# Adafruit_Trinket_5V.net
KiCad netlist of a schematic drawn in EAGLE
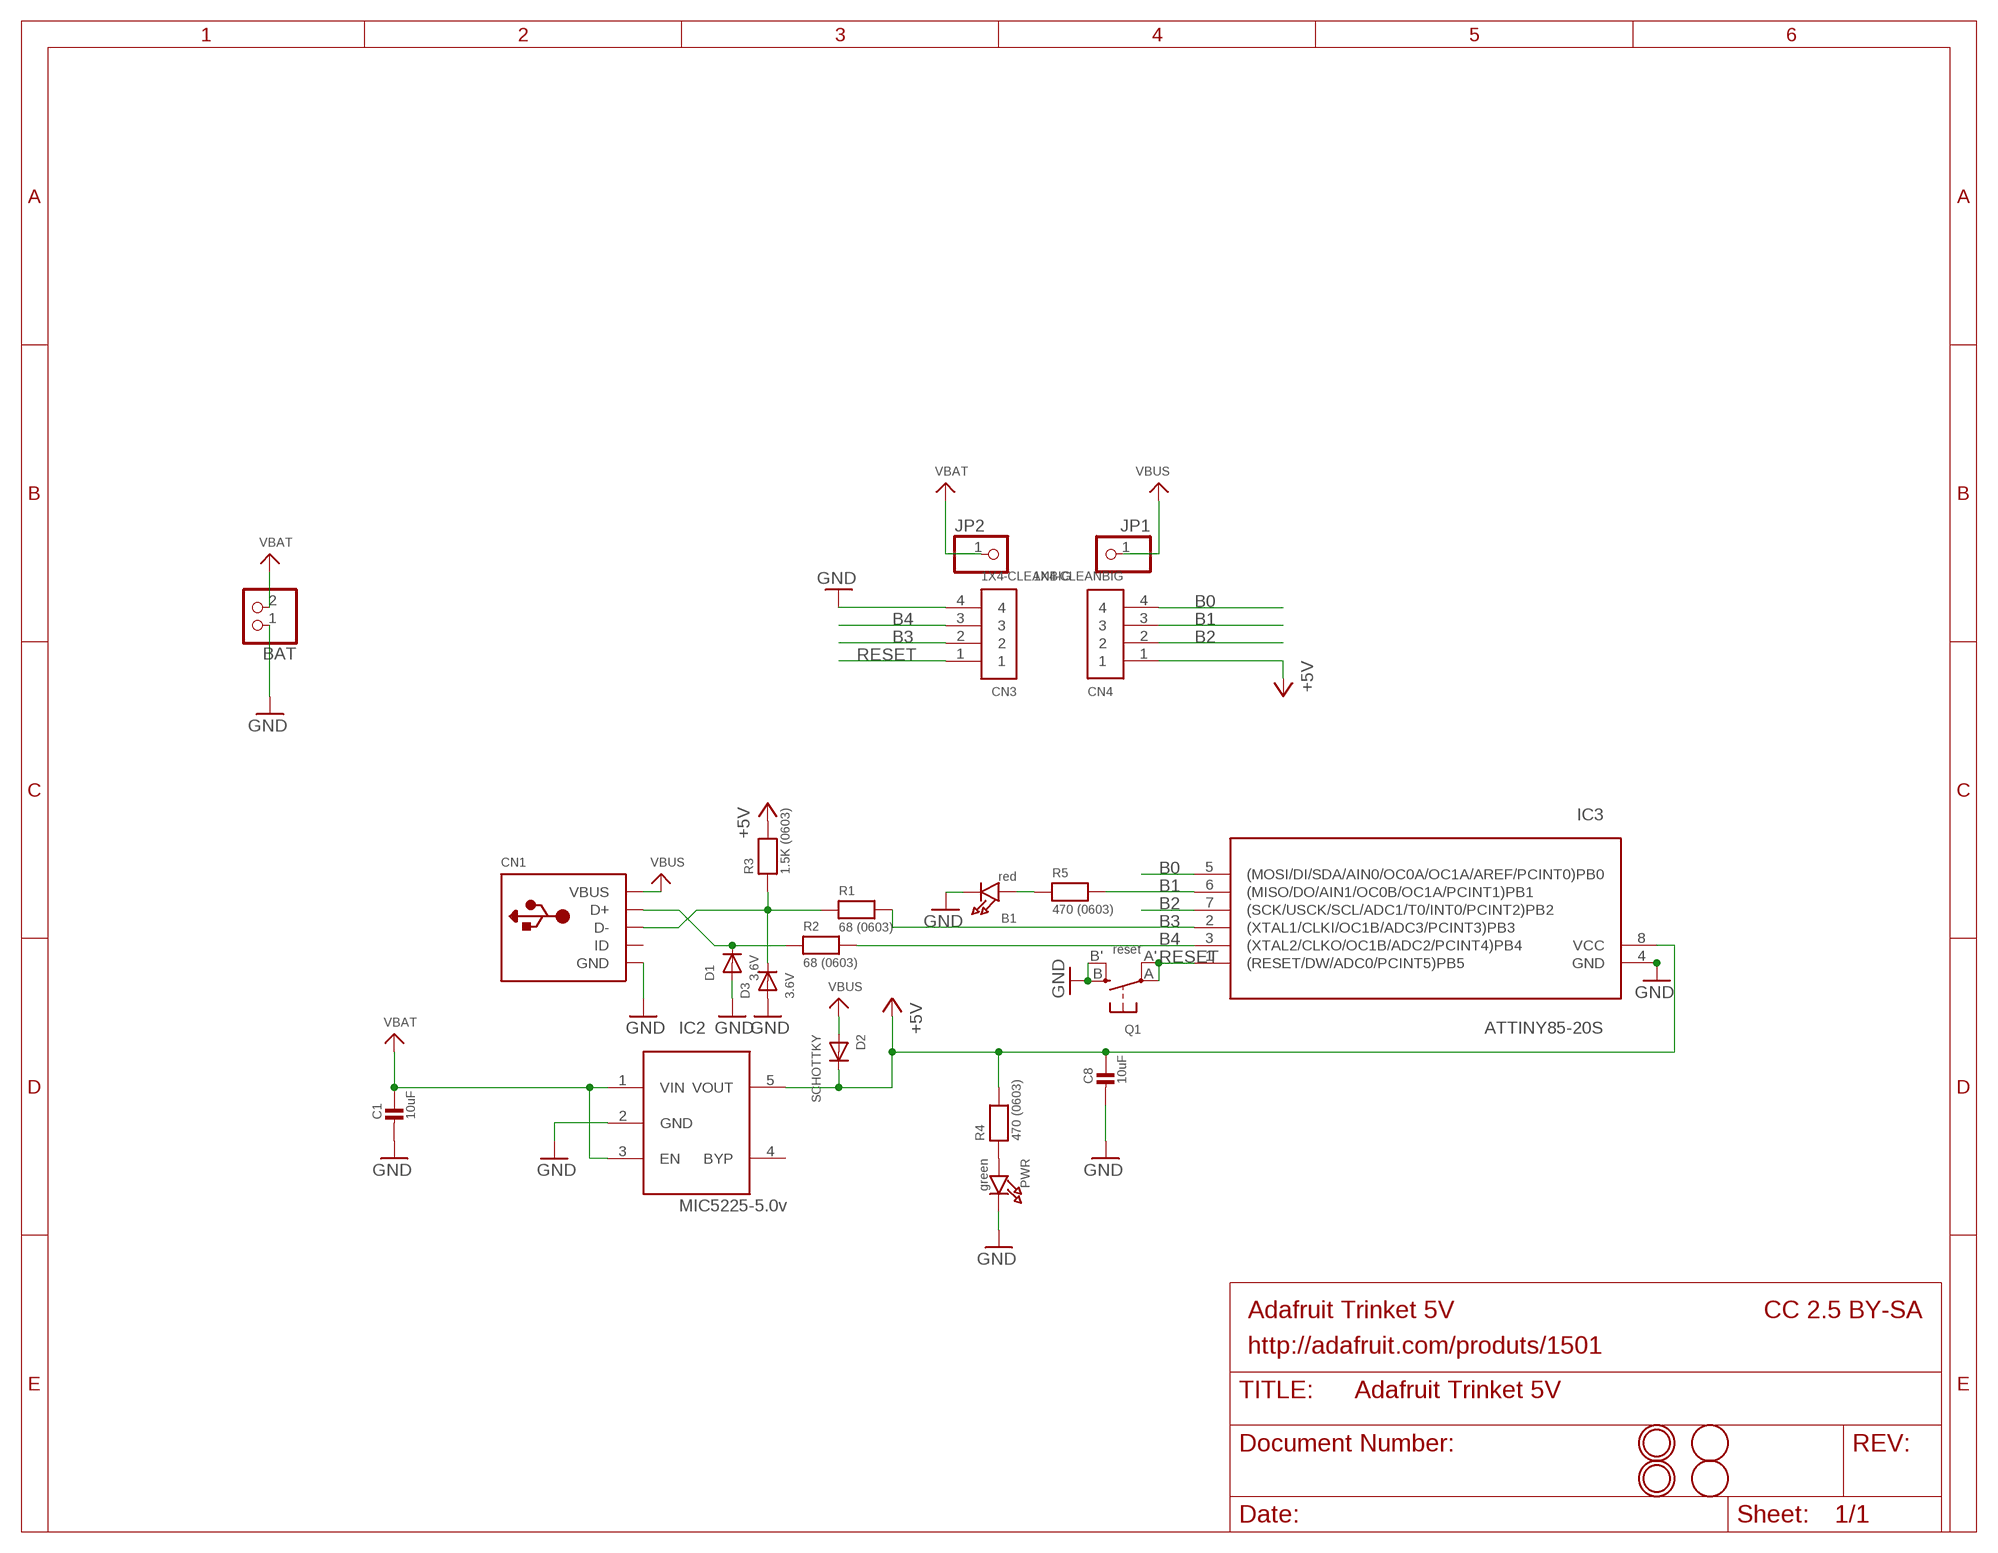
[diagram p0: schematic, sheet 1]

(export (version "E")
  (design (tool "Eeschema 10.0.6"))
  (components
    (comp (ref "B1")
      (value "red")
      (footprint "eagle-import:CHIPLED_0805_NOOUTLINE")
      (libsource (lib "eagle-import") (part "LED0805_NOOUTLINE"))
    )
    (comp (ref "BAT")
      (value "CON_JST_PH_2PIN")
      (footprint "eagle-import:JSTPH2")
      (libsource (lib "eagle-import") (part "CON_JST_PH_2PIN"))
    )
    (comp (ref "C1")
      (value "10uF")
      (footprint "eagle-import:0805-NO")
      (libsource (lib "eagle-import") (part "CAP_CERAMIC0805-NOOUTLINE"))
    )
    (comp (ref "C8")
      (value "10uF")
      (footprint "eagle-import:0805-NO")
      (libsource (lib "eagle-import") (part "CAP_CERAMIC0805-NOOUTLINE"))
    )
    (comp (ref "CN1")
      (value "USBMINIB")
      (footprint "eagle-import:USB-MINIB")
      (libsource (lib "eagle-import") (part "USBMINIB"))
    )
    (comp (ref "CN3")
      (value "1X4-CLEANBIG")
      (footprint "eagle-import:1X04-CLEANBIG")
      (libsource (lib "eagle-import") (part "1X4-CLEANBIG"))
    )
    (comp (ref "CN4")
      (value "1X4-CLEANBIG")
      (footprint "eagle-import:1X04-CLEANBIG")
      (libsource (lib "eagle-import") (part "1X4-CLEANBIG"))
    )
    (comp (ref "D1")
      (value "3.6V")
      (footprint "eagle-import:SOD-323")
      (libsource (lib "eagle-import") (part "DIODESOD-323"))
    )
    (comp (ref "D2")
      (value "SCHOTTKY")
      (footprint "eagle-import:SOD-123FL")
      (libsource (lib "eagle-import") (part "DIODE_SOD-123FL"))
    )
    (comp (ref "D3")
      (value "3.6V")
      (footprint "eagle-import:SOD-323")
      (libsource (lib "eagle-import") (part "DIODESOD-323"))
    )
    (comp (ref "IC2")
      (value "MIC5225-5.0v")
      (footprint "eagle-import:SOT23-5L")
      (libsource (lib "eagle-import") (part "LP298XS"))
    )
    (comp (ref "IC3")
      (value "ATTINY85-20S")
      (footprint "eagle-import:SOIC8")
      (libsource (lib "eagle-import") (part "ATTINY85SV-10"))
    )
    (comp (ref "JP1")
      (value "PINHD-1X1CB")
      (footprint "eagle-import:1X01-CLEANBIG")
      (libsource (lib "eagle-import") (part "PINHD-1X1CB"))
    )
    (comp (ref "JP2")
      (value "PINHD-1X1CB")
      (footprint "eagle-import:1X01-CLEANBIG")
      (libsource (lib "eagle-import") (part "PINHD-1X1CB"))
    )
    (comp (ref "PWR")
      (value "green")
      (footprint "eagle-import:CHIPLED_0805_NOOUTLINE")
      (libsource (lib "eagle-import") (part "LED0805_NOOUTLINE"))
    )
    (comp (ref "Q1")
      (value "reset")
      (footprint "eagle-import:BTN_KMR2_4.6X2.8")
      (libsource (lib "eagle-import") (part "SWITCH_TACT_SMT4.6X2.8"))
    )
    (comp (ref "R1")
      (value "68 (0603)")
      (footprint "eagle-import:0603-NO")
      (libsource (lib "eagle-import") (part "RESISTOR_0603_NOOUT"))
    )
    (comp (ref "R2")
      (value "68 (0603)")
      (footprint "eagle-import:0603-NO")
      (libsource (lib "eagle-import") (part "RESISTOR_0603_NOOUT"))
    )
    (comp (ref "R3")
      (value "1.5K (0603)")
      (footprint "eagle-import:0603-NO")
      (libsource (lib "eagle-import") (part "RESISTOR_0603_NOOUT"))
    )
    (comp (ref "R4")
      (value "470 (0603)")
      (footprint "eagle-import:0603-NO")
      (libsource (lib "eagle-import") (part "RESISTOR_0603_NOOUT"))
    )
    (comp (ref "R5")
      (value "470 (0603)")
      (footprint "eagle-import:0603-NO")
      (libsource (lib "eagle-import") (part "RESISTOR_0603_NOOUT"))
    )
    (comp (ref "U$1")
      (value "FIDUCIAL")
      (footprint "eagle-import:FIDUCIAL_1MM")
      (libsource (lib "eagle-import") (part "FIDUCIAL"))
    )
    (comp (ref "U$6")
      (value "FIDUCIAL")
      (footprint "eagle-import:FIDUCIAL_1MM")
      (libsource (lib "eagle-import") (part "FIDUCIAL"))
    )
    (comp (ref "U$8")
      (value "MOUNTINGHOLE2.0")
      (footprint "eagle-import:MOUNTINGHOLE_2.0_PLATED")
      (libsource (lib "eagle-import") (part "MOUNTINGHOLE2.0"))
    )
    (comp (ref "U$9")
      (value "MOUNTINGHOLE2.0")
      (footprint "eagle-import:MOUNTINGHOLE_2.0_PLATED")
      (libsource (lib "eagle-import") (part "MOUNTINGHOLE2.0"))
    )
  )
  (nets
    (net (code "1") (name "+5V") (class "Default")
      (node (ref "C8") (pin "1") (pinfunction "1_1") (pintype "passive"))
      (node (ref "CN4") (pin "1") (pinfunction "1_1") (pintype "bidirectional"))
      (node (ref "D2") (pin "C") (pinfunction "C_C") (pintype "passive"))
      (node (ref "IC2") (pin "5") (pinfunction "VOUT_5") (pintype "bidirectional"))
      (node (ref "IC3") (pin "8") (pinfunction "VCC_8") (pintype "bidirectional"))
      (node (ref "R3") (pin "2") (pinfunction "2_2") (pintype "passive"))
      (node (ref "R4") (pin "2") (pinfunction "2_2") (pintype "passive"))
    )
    (net (code "2") (name "/B0") (class "Default")
      (node (ref "CN4") (pin "4") (pinfunction "4_4") (pintype "bidirectional"))
      (node (ref "IC3") (pin "5") (pinfunction "(MOSI/DI/SDA/AIN0/OC0A/OC1A/AREF/PCINT0)PB0_5") (pintype "bidirectional"))
    )
    (net (code "3") (name "/B1") (class "Default")
      (node (ref "CN4") (pin "3") (pinfunction "3_3") (pintype "bidirectional"))
      (node (ref "IC3") (pin "6") (pinfunction "(MISO/DO/AIN1/OC0B/OC1A/PCINT1)PB1_6") (pintype "bidirectional"))
      (node (ref "R5") (pin "2") (pinfunction "2_2") (pintype "passive"))
    )
    (net (code "4") (name "/B2") (class "Default")
      (node (ref "CN4") (pin "2") (pinfunction "2_2") (pintype "bidirectional"))
      (node (ref "IC3") (pin "7") (pinfunction "(SCK/USCK/SCL/ADC1/T0/INT0/PCINT2)PB2_7") (pintype "bidirectional"))
    )
    (net (code "5") (name "/B3") (class "Default")
      (node (ref "CN3") (pin "2") (pinfunction "2_2") (pintype "bidirectional"))
      (node (ref "IC3") (pin "2") (pinfunction "(XTAL1/CLKI/OC1B/ADC3/PCINT3)PB3_2") (pintype "bidirectional"))
      (node (ref "R1") (pin "2") (pinfunction "2_2") (pintype "passive"))
    )
    (net (code "6") (name "/B4") (class "Default")
      (node (ref "CN3") (pin "3") (pinfunction "3_3") (pintype "bidirectional"))
      (node (ref "IC3") (pin "3") (pinfunction "(XTAL2/CLKO/OC1B/ADC2/PCINT4)PB4_3") (pintype "bidirectional"))
      (node (ref "R2") (pin "2") (pinfunction "2_2") (pintype "passive"))
    )
    (net (code "7") (name "/RESET") (class "Default")
      (node (ref "CN3") (pin "1") (pinfunction "1_1") (pintype "bidirectional"))
      (node (ref "IC3") (pin "1") (pinfunction "(RESET/DW/ADC0/PCINT5)PB5_1") (pintype "bidirectional"))
      (node (ref "Q1") (pin "A") (pinfunction "P_A") (pintype "passive"))
      (node (ref "Q1") (pin "A'") (pinfunction "P1_A'") (pintype "passive"))
    )
    (net (code "8") (name "GND") (class "Default")
      (node (ref "B1") (pin "C") (pinfunction "C_C") (pintype "passive"))
      (node (ref "BAT") (pin "1") (pinfunction "1_1") (pintype "passive"))
      (node (ref "C1") (pin "2") (pinfunction "2_2") (pintype "passive"))
      (node (ref "C8") (pin "2") (pinfunction "2_2") (pintype "passive"))
      (node (ref "CN1") (pin "GND") (pinfunction "GND_GND") (pintype "power_in"))
      (node (ref "CN1") (pin "GND1") (pinfunction "GND_GND1") (pintype "power_in"))
      (node (ref "CN1") (pin "GND2") (pinfunction "GND_GND2") (pintype "power_in"))
      (node (ref "CN1") (pin "GND3") (pinfunction "GND_GND3") (pintype "power_in"))
      (node (ref "CN1") (pin "GND4") (pinfunction "GND_GND4") (pintype "power_in"))
      (node (ref "CN3") (pin "4") (pinfunction "4_4") (pintype "bidirectional"))
      (node (ref "D1") (pin "A") (pinfunction "A_A") (pintype "passive"))
      (node (ref "D3") (pin "A") (pinfunction "A_A") (pintype "passive"))
      (node (ref "IC2") (pin "2") (pinfunction "GND_2") (pintype "bidirectional"))
      (node (ref "IC3") (pin "4") (pinfunction "GND_4") (pintype "bidirectional"))
      (node (ref "PWR") (pin "C") (pinfunction "C_C") (pintype "passive"))
      (node (ref "Q1") (pin "B") (pinfunction "S_B") (pintype "passive"))
      (node (ref "Q1") (pin "B'") (pinfunction "S1_B'") (pintype "passive"))
    )
    (net (code "9") (name "Net-(B1-PadA)") (class "Default")
      (node (ref "B1") (pin "A") (pinfunction "A_A") (pintype "passive"))
      (node (ref "R5") (pin "1") (pinfunction "1_1") (pintype "passive"))
    )
    (net (code "10") (name "Net-(CN1-PadD+)") (class "Default")
      (node (ref "CN1") (pin "D+") (pinfunction "D+_D+") (pintype "bidirectional"))
      (node (ref "D1") (pin "C") (pinfunction "C_C") (pintype "passive"))
      (node (ref "R2") (pin "1") (pinfunction "1_1") (pintype "passive"))
    )
    (net (code "11") (name "Net-(CN1-PadD-)") (class "Default")
      (node (ref "CN1") (pin "D-") (pinfunction "D-_D-") (pintype "bidirectional"))
      (node (ref "D3") (pin "C") (pinfunction "C_C") (pintype "passive"))
      (node (ref "R1") (pin "1") (pinfunction "1_1") (pintype "passive"))
      (node (ref "R3") (pin "1") (pinfunction "1_1") (pintype "passive"))
    )
    (net (code "12") (name "Net-(PWR-PadA)") (class "Default")
      (node (ref "PWR") (pin "A") (pinfunction "A_A") (pintype "passive"))
      (node (ref "R4") (pin "1") (pinfunction "1_1") (pintype "passive"))
    )
    (net (code "13") (name "VBAT") (class "Default")
      (node (ref "BAT") (pin "2") (pinfunction "2_2") (pintype "passive"))
      (node (ref "C1") (pin "1") (pinfunction "1_1") (pintype "passive"))
      (node (ref "IC2") (pin "1") (pinfunction "VIN_1") (pintype "bidirectional"))
      (node (ref "IC2") (pin "3") (pinfunction "EN_3") (pintype "bidirectional"))
      (node (ref "JP2") (pin "1") (pinfunction "1_1") (pintype "passive"))
    )
    (net (code "14") (name "VBUS") (class "Default")
      (node (ref "CN1") (pin "VBUS") (pinfunction "VBUS_VBUS") (pintype "power_in"))
      (node (ref "D2") (pin "A") (pinfunction "A_A") (pintype "passive"))
      (node (ref "JP1") (pin "1") (pinfunction "1_1") (pintype "passive"))
    )
    (net (code "15") (name "unconnected-(CN1-PadID)") (class "Default")
      (node (ref "CN1") (pin "ID") (pinfunction "ID_ID") (pintype "bidirectional"))
    )
    (net (code "16") (name "unconnected-(IC2-BYP-Pad4)") (class "Default")
      (node (ref "IC2") (pin "4") (pinfunction "BYP_4") (pintype "bidirectional"))
    )
  )
)
